# ADC_CH.net
KiCad netlist of a schematic drawn in Altium Designer
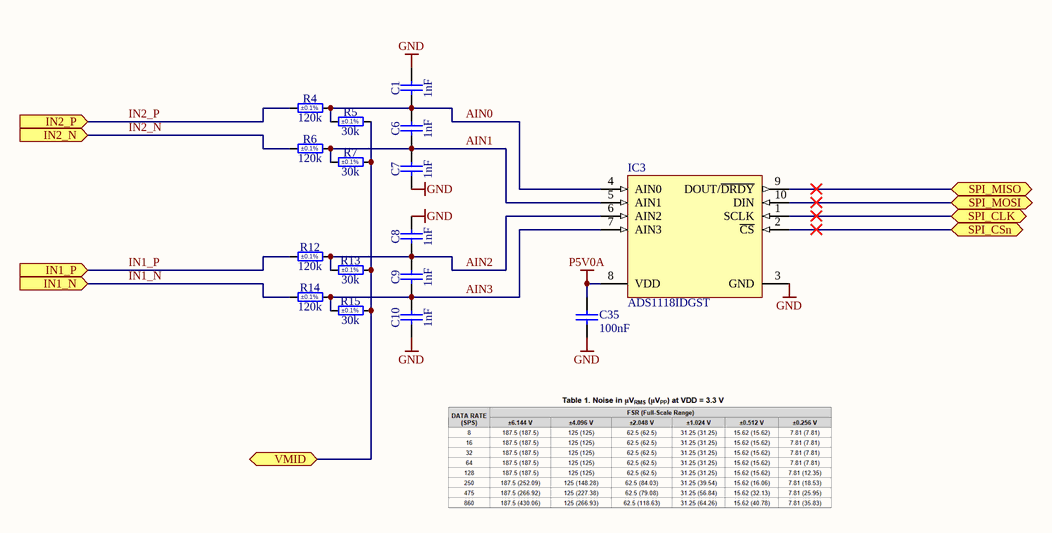
[diagram p0: ADC_CH.SchDoc]

(export (version "E")
  (design (tool "Eeschema 10.0.6"))
  (components
    (comp (ref "C1")
      (value "1nF")
      (footprint "CAPC1608X90N")
      (description "Non-polarised capacitor")
      (fields
        (field (name "PART NUMBER") "CC0603_1NF_50V_5%_NP0")
        (field (name "VOLTAGE") "50V")
        (field (name "AUTHOR") "CERN DEM JLC")
      )
      (libsource (lib "Capacitors") (part "Capacitor - non polarized"))
    )
    (comp (ref "C6")
      (value "1nF")
      (footprint "CAPC1608X90N")
      (description "Non-polarised capacitor")
      (fields
        (field (name "PART NUMBER") "CC0603_1NF_50V_5%_NP0")
        (field (name "VOLTAGE") "50V")
        (field (name "AUTHOR") "CERN DEM JLC")
      )
      (libsource (lib "Capacitors") (part "Capacitor - non polarized"))
    )
    (comp (ref "C7")
      (value "1nF")
      (footprint "CAPC1608X90N")
      (description "Non-polarised capacitor")
      (fields
        (field (name "PART NUMBER") "CC0603_1NF_50V_5%_NP0")
        (field (name "VOLTAGE") "50V")
        (field (name "AUTHOR") "CERN DEM JLC")
      )
      (libsource (lib "Capacitors") (part "Capacitor - non polarized"))
    )
    (comp (ref "C8")
      (value "1nF")
      (footprint "CAPC1608X90N")
      (description "Non-polarised capacitor")
      (fields
        (field (name "PART NUMBER") "CC0603_1NF_50V_5%_NP0")
        (field (name "VOLTAGE") "50V")
        (field (name "AUTHOR") "CERN DEM JLC")
      )
      (libsource (lib "Capacitors") (part "Capacitor - non polarized"))
    )
    (comp (ref "C9")
      (value "1nF")
      (footprint "CAPC1608X90N")
      (description "Non-polarised capacitor")
      (fields
        (field (name "PART NUMBER") "CC0603_1NF_50V_5%_NP0")
        (field (name "VOLTAGE") "50V")
        (field (name "AUTHOR") "CERN DEM JLC")
      )
      (libsource (lib "Capacitors") (part "Capacitor - non polarized"))
    )
    (comp (ref "C10")
      (value "1nF")
      (footprint "CAPC1608X90N")
      (description "Non-polarised capacitor")
      (fields
        (field (name "PART NUMBER") "CC0603_1NF_50V_5%_NP0")
        (field (name "VOLTAGE") "50V")
        (field (name "AUTHOR") "CERN DEM JLC")
      )
      (libsource (lib "Capacitors") (part "Capacitor - non polarized"))
    )
    (comp (ref "C35")
      (value "100nF")
      (footprint "CAPC1005X55N")
      (description "Non-polarised capacitor")
      (fields
        (field (name "PART NUMBER") "CC0402_100NF_16V_10%_X7R")
        (field (name "VOLTAGE") "16V")
        (field (name "AUTHOR") "CERN DEM JLC")
      )
      (libsource (lib "Capacitors") (part "Capacitor - non polarized"))
    )
    (comp (ref "IC3")
      (value "ADS1118IDGST")
      (footprint "SOP50P490X110-10N")
      (description "Quad Channel Single ADC Delta-Sigma 860sps 16-bit Serial 10-Pin VSSOP T/R")
      (fields (field (name "MANUFACTURER") "Texas Instruments"))
      (libsource (lib "mb") (part "ADS1118IDGST"))
    )
    (comp (ref "R4")
      (value "120k")
      (footprint "RESC3216X65N")
      (description "Resistor - 0.1%")
      (fields
        (field (name "TOLERANCE") "±0.1%")
        (field (name "PART NUMBER") "R1206_120K_0.1%_0.25W_25PPM")
        (field (name "POWER") "0.25W")
        (field (name "AUTHOR") "CERN DEM JLC")
      )
      (libsource (lib "Resistors") (part "Resistor - 0.1%"))
    )
    (comp (ref "R5")
      (value "30k")
      (footprint "RESC1608X55N")
      (description "Resistor - 0.1%")
      (fields
        (field (name "TOLERANCE") "±0.1%")
        (field (name "PART NUMBER") "R0603_30K_0.1%_0.063W_25PPM")
        (field (name "POWER") "0.063W")
        (field (name "AUTHOR") "CERN DEM JMW")
      )
      (libsource (lib "Resistors") (part "Resistor - 0.1%"))
    )
    (comp (ref "R6")
      (value "120k")
      (footprint "RESC3216X65N")
      (description "Resistor - 0.1%")
      (fields
        (field (name "TOLERANCE") "±0.1%")
        (field (name "PART NUMBER") "R1206_120K_0.1%_0.25W_25PPM")
        (field (name "POWER") "0.25W")
        (field (name "AUTHOR") "CERN DEM JLC")
      )
      (libsource (lib "Resistors") (part "Resistor - 0.1%"))
    )
    (comp (ref "R7")
      (value "30k")
      (footprint "RESC1608X55N")
      (description "Resistor - 0.1%")
      (fields
        (field (name "TOLERANCE") "±0.1%")
        (field (name "PART NUMBER") "R0603_30K_0.1%_0.063W_25PPM")
        (field (name "POWER") "0.063W")
        (field (name "AUTHOR") "CERN DEM JMW")
      )
      (libsource (lib "Resistors") (part "Resistor - 0.1%"))
    )
    (comp (ref "R12")
      (value "120k")
      (footprint "RESC3216X65N")
      (description "Resistor - 0.1%")
      (fields
        (field (name "TOLERANCE") "±0.1%")
        (field (name "PART NUMBER") "R1206_120K_0.1%_0.25W_25PPM")
        (field (name "POWER") "0.25W")
        (field (name "AUTHOR") "CERN DEM JLC")
      )
      (libsource (lib "Resistors") (part "Resistor - 0.1%"))
    )
    (comp (ref "R13")
      (value "30k")
      (footprint "RESC1608X55N")
      (description "Resistor - 0.1%")
      (fields
        (field (name "TOLERANCE") "±0.1%")
        (field (name "PART NUMBER") "R0603_30K_0.1%_0.063W_25PPM")
        (field (name "POWER") "0.063W")
        (field (name "AUTHOR") "CERN DEM JMW")
      )
      (libsource (lib "Resistors") (part "Resistor - 0.1%"))
    )
    (comp (ref "R14")
      (value "120k")
      (footprint "RESC3216X65N")
      (description "Resistor - 0.1%")
      (fields
        (field (name "TOLERANCE") "±0.1%")
        (field (name "PART NUMBER") "R1206_120K_0.1%_0.25W_25PPM")
        (field (name "POWER") "0.25W")
        (field (name "AUTHOR") "CERN DEM JLC")
      )
      (libsource (lib "Resistors") (part "Resistor - 0.1%"))
    )
    (comp (ref "R15")
      (value "30k")
      (footprint "RESC1608X55N")
      (description "Resistor - 0.1%")
      (fields
        (field (name "TOLERANCE") "±0.1%")
        (field (name "PART NUMBER") "R0603_30K_0.1%_0.063W_25PPM")
        (field (name "POWER") "0.063W")
        (field (name "AUTHOR") "CERN DEM JMW")
      )
      (libsource (lib "Resistors") (part "Resistor - 0.1%"))
    )
  )
  (nets
    (net (code "1") (name "/AIN0") (class "Default")
      (node (ref "C1") (pin "1") (pinfunction "1_1") (pintype "passive"))
      (node (ref "C6") (pin "2") (pinfunction "2_2") (pintype "passive"))
      (node (ref "IC3") (pin "4") (pinfunction "AIN0_4") (pintype "input"))
      (node (ref "R4") (pin "2") (pinfunction "2_2") (pintype "passive"))
      (node (ref "R5") (pin "1") (pinfunction "1_1") (pintype "passive"))
    )
    (net (code "2") (name "/AIN1") (class "Default")
      (node (ref "C6") (pin "1") (pinfunction "1_1") (pintype "passive"))
      (node (ref "C7") (pin "2") (pinfunction "2_2") (pintype "passive"))
      (node (ref "IC3") (pin "5") (pinfunction "AIN1_5") (pintype "input"))
      (node (ref "R6") (pin "2") (pinfunction "2_2") (pintype "passive"))
      (node (ref "R7") (pin "1") (pinfunction "1_1") (pintype "passive"))
    )
    (net (code "3") (name "/AIN2") (class "Default")
      (node (ref "C8") (pin "1") (pinfunction "1_1") (pintype "passive"))
      (node (ref "C9") (pin "2") (pinfunction "2_2") (pintype "passive"))
      (node (ref "IC3") (pin "6") (pinfunction "AIN2_6") (pintype "input"))
      (node (ref "R12") (pin "2") (pinfunction "2_2") (pintype "passive"))
      (node (ref "R13") (pin "1") (pinfunction "1_1") (pintype "passive"))
    )
    (net (code "4") (name "/AIN3") (class "Default")
      (node (ref "C10") (pin "2") (pinfunction "2_2") (pintype "passive"))
      (node (ref "C9") (pin "1") (pinfunction "1_1") (pintype "passive"))
      (node (ref "IC3") (pin "7") (pinfunction "AIN3_7") (pintype "input"))
      (node (ref "R14") (pin "2") (pinfunction "2_2") (pintype "passive"))
      (node (ref "R15") (pin "1") (pinfunction "1_1") (pintype "passive"))
    )
    (net (code "5") (name "/IN1_N") (class "Default")
      (node (ref "R14") (pin "1") (pinfunction "1_1") (pintype "passive"))
    )
    (net (code "6") (name "/IN1_P") (class "Default")
      (node (ref "R12") (pin "1") (pinfunction "1_1") (pintype "passive"))
    )
    (net (code "7") (name "/IN2_N") (class "Default")
      (node (ref "R6") (pin "1") (pinfunction "1_1") (pintype "passive"))
    )
    (net (code "8") (name "/IN2_P") (class "Default")
      (node (ref "R4") (pin "1") (pinfunction "1_1") (pintype "passive"))
    )
    (net (code "9") (name "/SPI_CLK") (class "Default")
      (node (ref "IC3") (pin "1") (pinfunction "SCLK_1") (pintype "input"))
    )
    (net (code "10") (name "/SPI_CSn") (class "Default")
      (node (ref "IC3") (pin "2") (pinfunction "~{CS}_2") (pintype "input"))
    )
    (net (code "11") (name "/SPI_MISO") (class "Default")
      (node (ref "IC3") (pin "9") (pinfunction "DOUT/~{DRDY}_9") (pintype "output"))
    )
    (net (code "12") (name "/SPI_MOSI") (class "Default")
      (node (ref "IC3") (pin "10") (pinfunction "DIN_10") (pintype "input"))
    )
    (net (code "13") (name "/VMID") (class "Default")
      (node (ref "R13") (pin "2") (pinfunction "2_2") (pintype "passive"))
      (node (ref "R15") (pin "2") (pinfunction "2_2") (pintype "passive"))
      (node (ref "R5") (pin "2") (pinfunction "2_2") (pintype "passive"))
      (node (ref "R7") (pin "2") (pinfunction "2_2") (pintype "passive"))
    )
    (net (code "14") (name "GND") (class "Default")
      (node (ref "C1") (pin "2") (pinfunction "2_2") (pintype "passive"))
      (node (ref "C10") (pin "1") (pinfunction "1_1") (pintype "passive"))
      (node (ref "C35") (pin "1") (pinfunction "1_1") (pintype "passive"))
      (node (ref "C7") (pin "1") (pinfunction "1_1") (pintype "passive"))
      (node (ref "C8") (pin "2") (pinfunction "2_2") (pintype "passive"))
      (node (ref "IC3") (pin "3") (pinfunction "GND_3") (pintype "power_in"))
    )
    (net (code "15") (name "P5V0A") (class "Default")
      (node (ref "C35") (pin "2") (pinfunction "2_2") (pintype "passive"))
      (node (ref "IC3") (pin "8") (pinfunction "VDD_8") (pintype "power_in"))
    )
  )
)
